# contra1568_X_Y.net
KiCad netlist of a schematic drawn in EAGLE
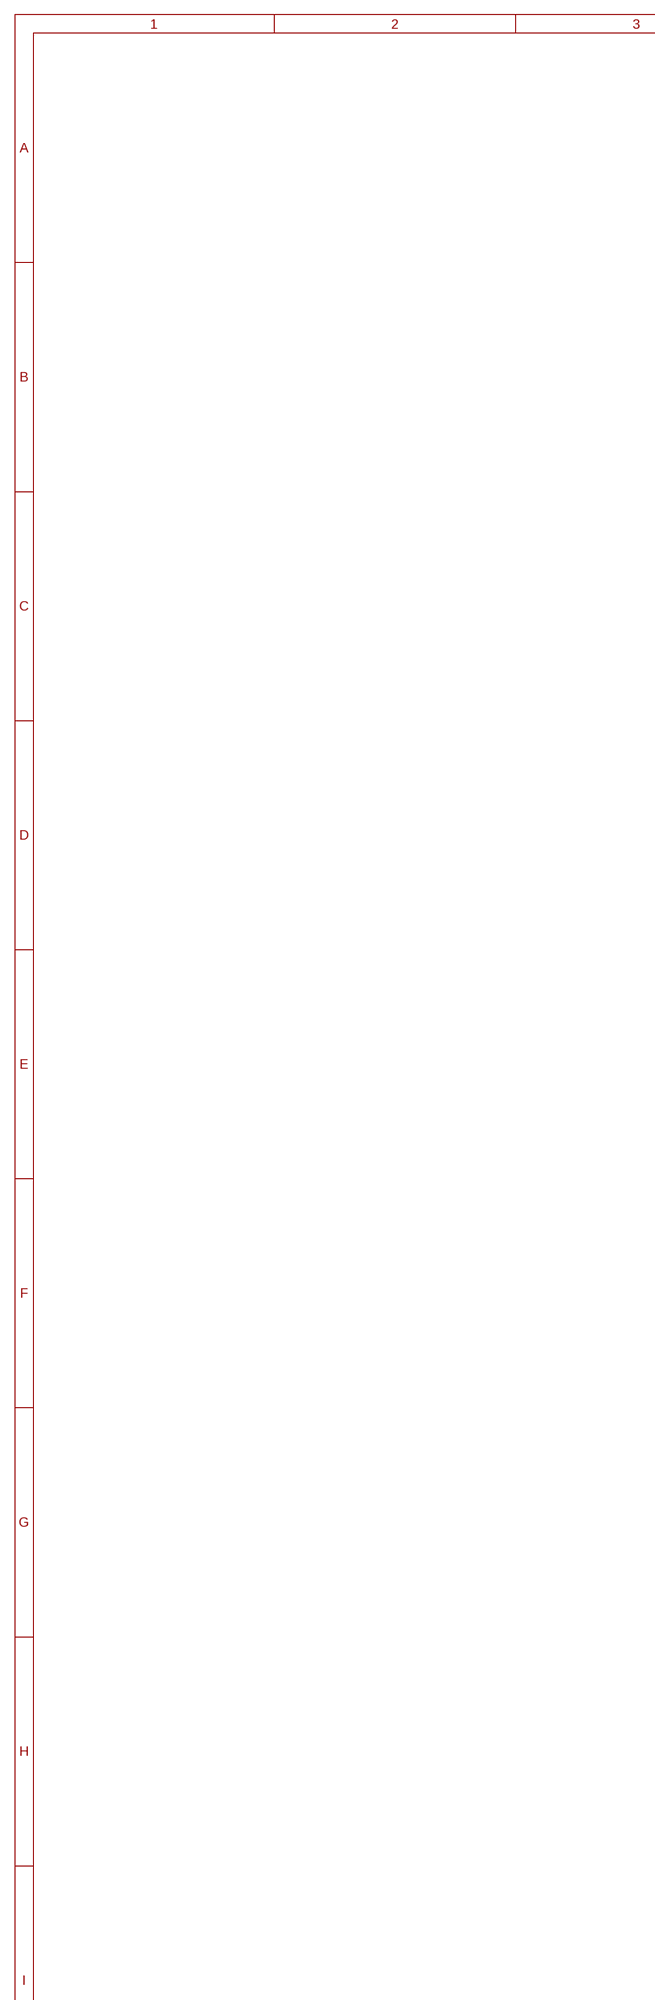
[diagram p0: schematic, sheet 1, part 1 of 2]
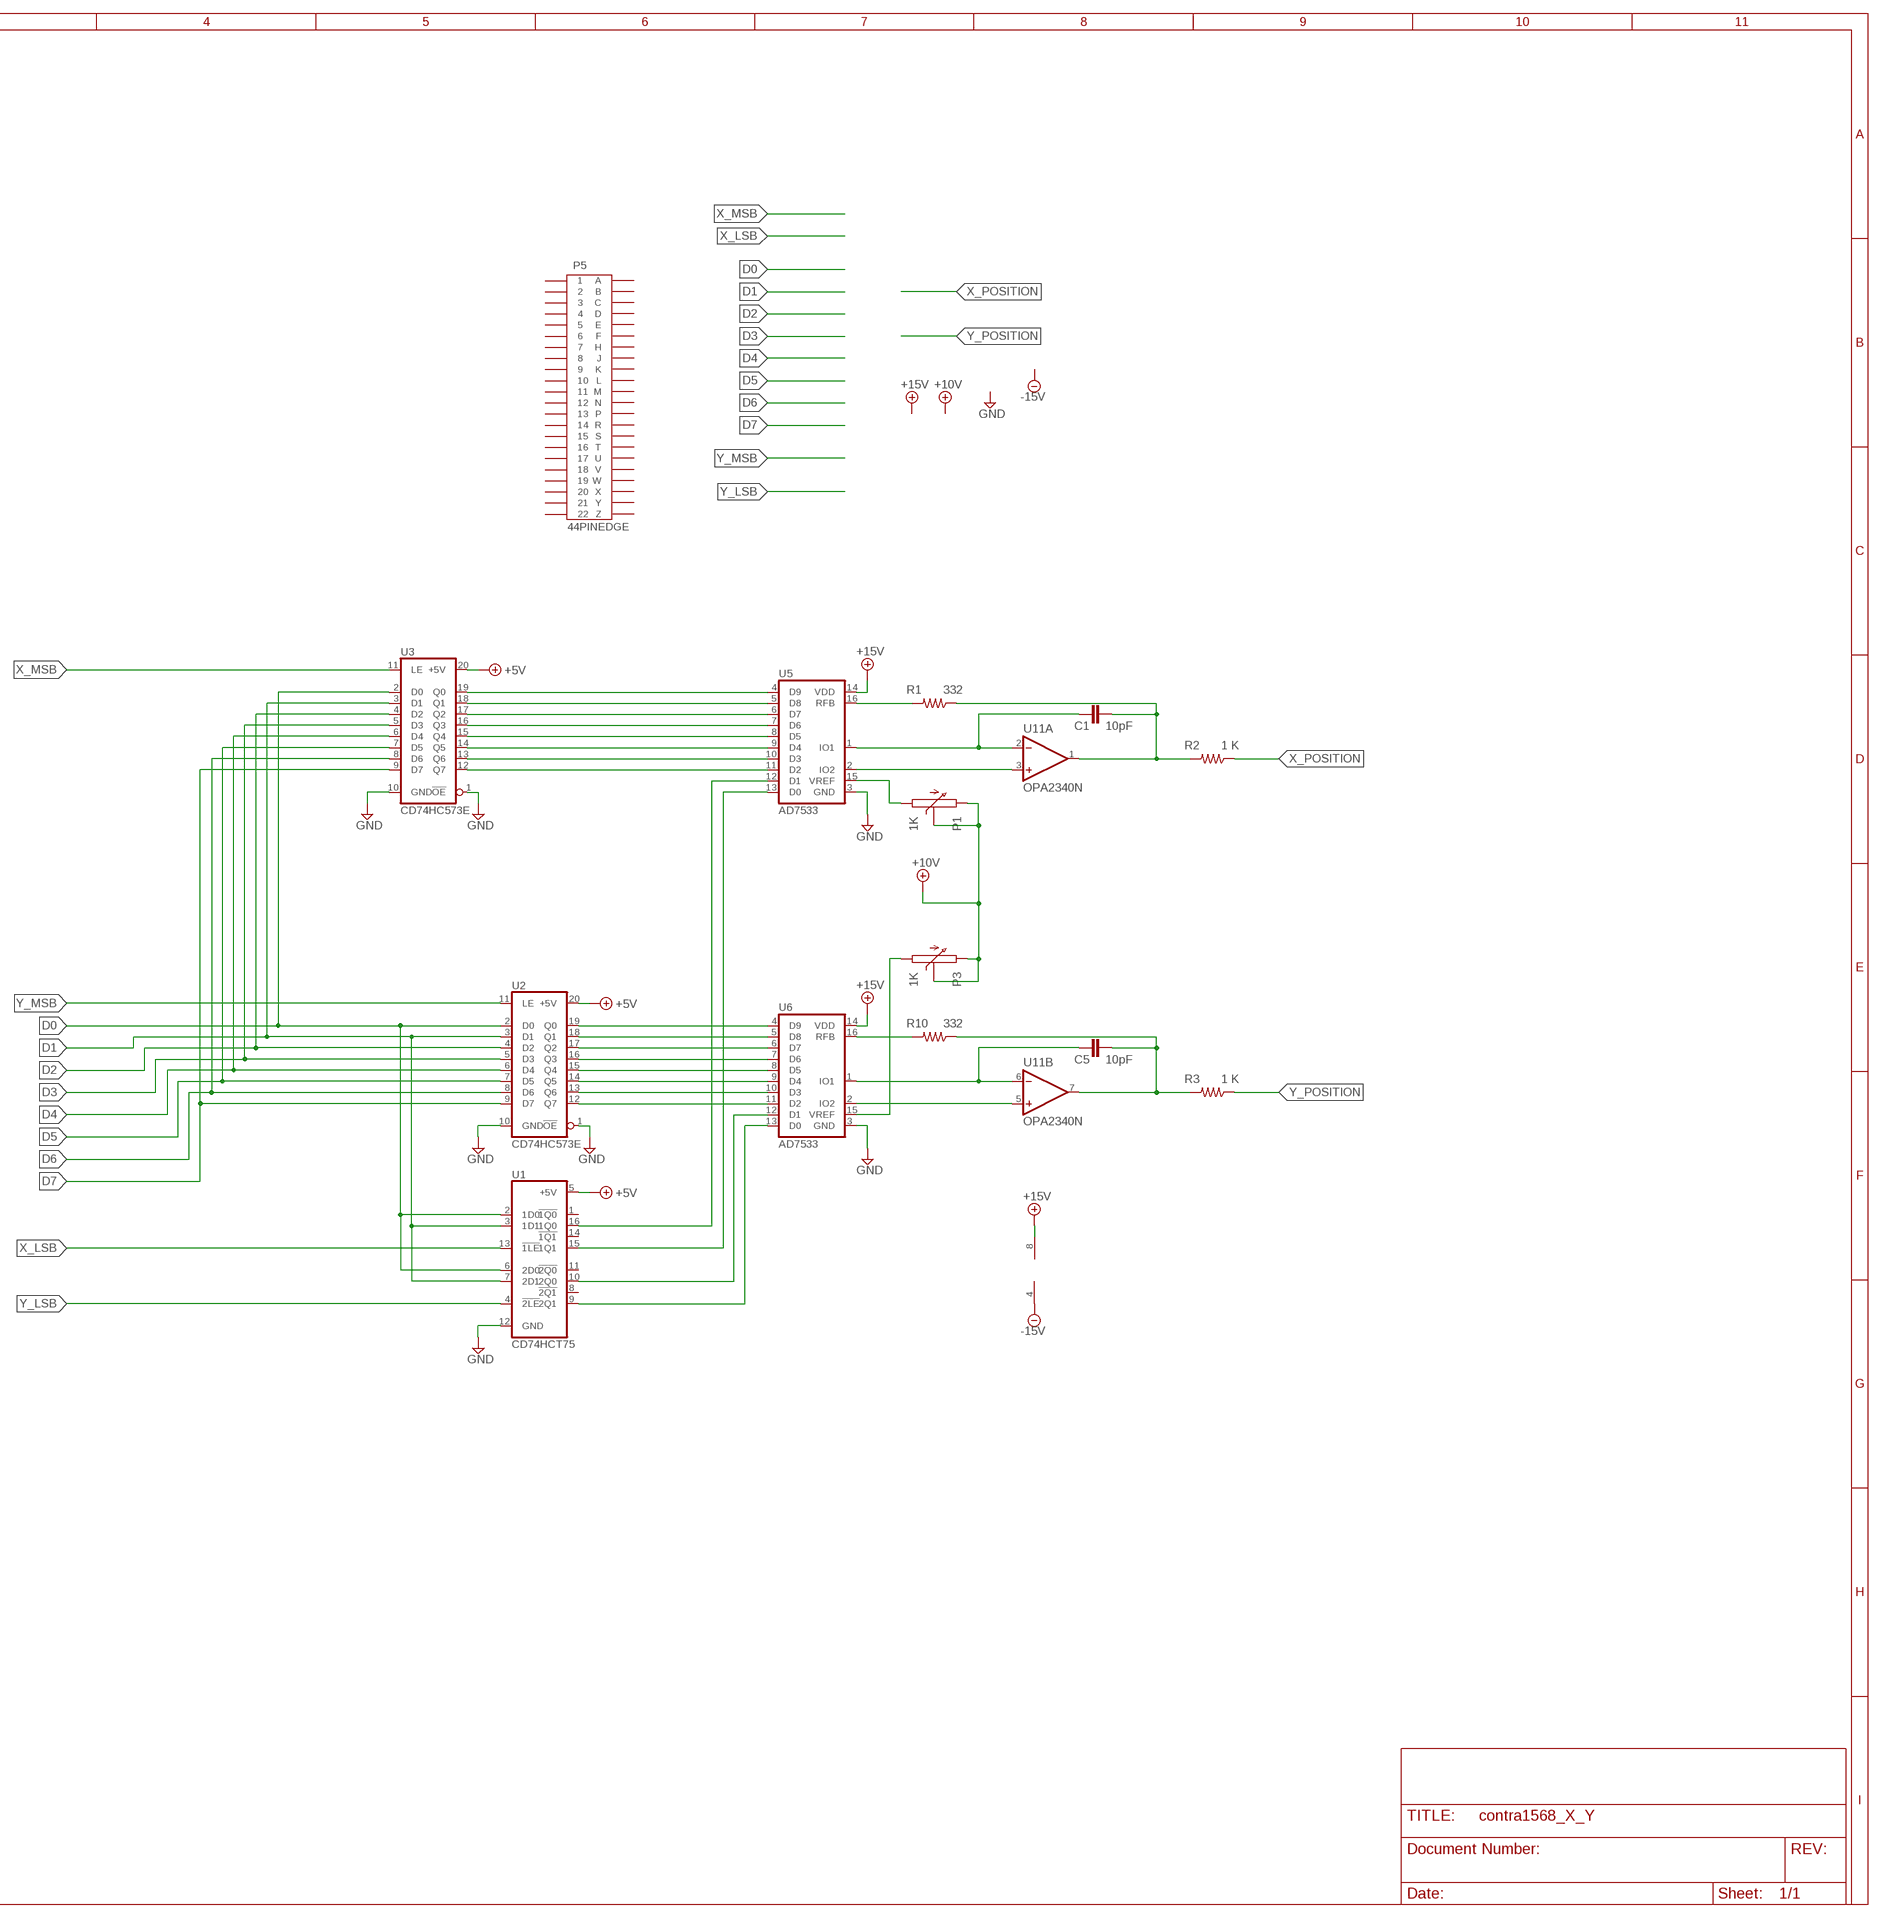
[diagram p1: schematic, sheet 1, part 2 of 2]

(export (version "E")
  (design (tool "Eeschema 10.0.6"))
  (components
    (comp (ref "C1")
      (value "10pF")
      (footprint "eagle-import:C2.5")
      (libsource (lib "eagle-import") (part "C-0.1"))
    )
    (comp (ref "C5")
      (value "10pF")
      (footprint "eagle-import:C2.5")
      (libsource (lib "eagle-import") (part "C-0.1"))
    )
    (comp (ref "P1")
      (value "1K")
      (footprint "eagle-import:3006P")
      (libsource (lib "eagle-import") (part "POT-3006P"))
    )
    (comp (ref "P3")
      (value "1K")
      (footprint "eagle-import:3006P")
      (libsource (lib "eagle-import") (part "POT-3006P"))
    )
    (comp (ref "P5")
      (value "44PINEDGE")
      (footprint "eagle-import:44PINEDGE")
      (libsource (lib "eagle-import") (part "44PINEDGE"))
    )
    (comp (ref "R1")
      (value "332")
      (footprint "eagle-import:0207_10")
      (libsource (lib "eagle-import") (part "R-1/4WATT"))
    )
    (comp (ref "R2")
      (value "1 K")
      (footprint "eagle-import:0207_10")
      (libsource (lib "eagle-import") (part "R-1/4WATT"))
    )
    (comp (ref "R3")
      (value "1 K")
      (footprint "eagle-import:0207_10")
      (libsource (lib "eagle-import") (part "R-1/4WATT"))
    )
    (comp (ref "R10")
      (value "332")
      (footprint "eagle-import:0207_10")
      (libsource (lib "eagle-import") (part "R-1/4WATT"))
    )
    (comp (ref "U1")
      (value "CD74HCT75")
      (footprint "eagle-import:DIP-16")
      (libsource (lib "eagle-import") (part "CD74HCT75"))
    )
    (comp (ref "U2")
      (value "CD74HC573E")
      (footprint "eagle-import:DIP-20")
      (libsource (lib "eagle-import") (part "CD74HC573E"))
    )
    (comp (ref "U3")
      (value "CD74HC573E")
      (footprint "eagle-import:DIP-20")
      (libsource (lib "eagle-import") (part "CD74HC573E"))
    )
    (comp (ref "U5")
      (value "AD7533")
      (footprint "eagle-import:DIP-16")
      (libsource (lib "eagle-import") (part "AD7533"))
    )
    (comp (ref "U6")
      (value "AD7533")
      (footprint "eagle-import:DIP-16")
      (libsource (lib "eagle-import") (part "AD7533"))
    )
    (comp (ref "U11")
      (value "OPA2340N")
      (footprint "eagle-import:DIP-08")
      (fields (field (name "PN") "OPA2340PA"))
      (libsource (lib "eagle-import") (part "OPA2340N"))
    )
  )
  (nets
    (net (code "1") (name "+5V") (class "Default")
      (node (ref "U1") (pin "5") (pinfunction "+5V_5") (pintype "power_in"))
      (node (ref "U2") (pin "20") (pinfunction "+5V_20") (pintype "power_in"))
      (node (ref "U3") (pin "20") (pinfunction "+5V_20") (pintype "power_in"))
    )
    (net (code "2") (name "+10V") (class "Default")
      (node (ref "P1") (pin "2") (pinfunction "S_2") (pintype "passive"))
      (node (ref "P1") (pin "3") (pinfunction "E_3") (pintype "passive"))
      (node (ref "P3") (pin "2") (pinfunction "S_2") (pintype "passive"))
      (node (ref "P3") (pin "3") (pinfunction "E_3") (pintype "passive"))
    )
    (net (code "3") (name "+15V") (class "Default")
      (node (ref "U11") (pin "8") (pinfunction "V+_8") (pintype "power_in"))
      (node (ref "U5") (pin "14") (pinfunction "VDD_14") (pintype "power_in"))
      (node (ref "U6") (pin "14") (pinfunction "VDD_14") (pintype "power_in"))
    )
    (net (code "4") (name "-15V") (class "Default")
      (node (ref "U11") (pin "4") (pinfunction "V-_4") (pintype "power_in"))
    )
    (net (code "5") (name "D0") (class "Default")
      (node (ref "U1") (pin "2") (pinfunction "1D0_2") (pintype "input"))
      (node (ref "U1") (pin "6") (pinfunction "2D0_6") (pintype "input"))
      (node (ref "U2") (pin "2") (pinfunction "D0_2") (pintype "input"))
      (node (ref "U3") (pin "2") (pinfunction "D0_2") (pintype "input"))
    )
    (net (code "6") (name "D1") (class "Default")
      (node (ref "U1") (pin "3") (pinfunction "1D1_3") (pintype "input"))
      (node (ref "U1") (pin "7") (pinfunction "2D1_7") (pintype "input"))
      (node (ref "U2") (pin "3") (pinfunction "D1_3") (pintype "input"))
      (node (ref "U3") (pin "3") (pinfunction "D1_3") (pintype "input"))
    )
    (net (code "7") (name "D2") (class "Default")
      (node (ref "U2") (pin "4") (pinfunction "D2_4") (pintype "input"))
      (node (ref "U3") (pin "4") (pinfunction "D2_4") (pintype "input"))
    )
    (net (code "8") (name "D3") (class "Default")
      (node (ref "U2") (pin "5") (pinfunction "D3_5") (pintype "input"))
      (node (ref "U3") (pin "5") (pinfunction "D3_5") (pintype "input"))
    )
    (net (code "9") (name "D4") (class "Default")
      (node (ref "U2") (pin "6") (pinfunction "D4_6") (pintype "input"))
      (node (ref "U3") (pin "6") (pinfunction "D4_6") (pintype "input"))
    )
    (net (code "10") (name "D5") (class "Default")
      (node (ref "U2") (pin "7") (pinfunction "D5_7") (pintype "input"))
      (node (ref "U3") (pin "7") (pinfunction "D5_7") (pintype "input"))
    )
    (net (code "11") (name "D6") (class "Default")
      (node (ref "U2") (pin "8") (pinfunction "D6_8") (pintype "input"))
      (node (ref "U3") (pin "8") (pinfunction "D6_8") (pintype "input"))
    )
    (net (code "12") (name "D7") (class "Default")
      (node (ref "U2") (pin "9") (pinfunction "D7_9") (pintype "input"))
      (node (ref "U3") (pin "9") (pinfunction "D7_9") (pintype "input"))
    )
    (net (code "13") (name "GND") (class "Default")
      (node (ref "U1") (pin "12") (pinfunction "GND_12") (pintype "power_in"))
      (node (ref "U2") (pin "1") (pinfunction "~{OE}_1") (pintype "input"))
      (node (ref "U2") (pin "10") (pinfunction "GND_10") (pintype "power_in"))
      (node (ref "U3") (pin "1") (pinfunction "~{OE}_1") (pintype "input"))
      (node (ref "U3") (pin "10") (pinfunction "GND_10") (pintype "power_in"))
      (node (ref "U5") (pin "3") (pinfunction "GND_3") (pintype "power_in"))
      (node (ref "U6") (pin "3") (pinfunction "GND_3") (pintype "power_in"))
    )
    (net (code "14") (name "Net-(P1-A)") (class "Default")
      (node (ref "P1") (pin "1") (pinfunction "A_1") (pintype "passive"))
      (node (ref "U5") (pin "15") (pinfunction "VREF_15") (pintype "power_in"))
    )
    (net (code "15") (name "Net-(P3-A)") (class "Default")
      (node (ref "P3") (pin "1") (pinfunction "A_1") (pintype "passive"))
      (node (ref "U6") (pin "15") (pinfunction "VREF_15") (pintype "power_in"))
    )
    (net (code "16") (name "Net-(R1-P$1)") (class "Default")
      (node (ref "C1") (pin "2") (pinfunction "2_2") (pintype "passive"))
      (node (ref "R1") (pin "1") (pinfunction "P$1_1") (pintype "passive"))
      (node (ref "R2") (pin "2") (pinfunction "P$2_2") (pintype "passive"))
      (node (ref "U11") (pin "1") (pinfunction "OUT_1") (pintype "output"))
    )
    (net (code "17") (name "Net-(R1-P$2)") (class "Default")
      (node (ref "R1") (pin "2") (pinfunction "P$2_2") (pintype "passive"))
      (node (ref "U5") (pin "16") (pinfunction "RFB_16") (pintype "input"))
    )
    (net (code "18") (name "Net-(R10-P$1)") (class "Default")
      (node (ref "C5") (pin "2") (pinfunction "2_2") (pintype "passive"))
      (node (ref "R10") (pin "1") (pinfunction "P$1_1") (pintype "passive"))
      (node (ref "R3") (pin "2") (pinfunction "P$2_2") (pintype "passive"))
      (node (ref "U11") (pin "7") (pinfunction "OUT_7") (pintype "output"))
    )
    (net (code "19") (name "Net-(R10-P$2)") (class "Default")
      (node (ref "R10") (pin "2") (pinfunction "P$2_2") (pintype "passive"))
      (node (ref "U6") (pin "16") (pinfunction "RFB_16") (pintype "input"))
    )
    (net (code "20") (name "Net-(U1-1Q0)") (class "Default")
      (node (ref "U1") (pin "16") (pinfunction "1Q0_16") (pintype "output"))
      (node (ref "U5") (pin "12") (pinfunction "D1_12") (pintype "input"))
    )
    (net (code "21") (name "Net-(U1-1Q1)") (class "Default")
      (node (ref "U1") (pin "15") (pinfunction "1Q1_15") (pintype "output"))
      (node (ref "U5") (pin "13") (pinfunction "D0_13") (pintype "input"))
    )
    (net (code "22") (name "Net-(U1-2Q0)") (class "Default")
      (node (ref "U1") (pin "10") (pinfunction "2Q0_10") (pintype "output"))
      (node (ref "U6") (pin "12") (pinfunction "D1_12") (pintype "input"))
    )
    (net (code "23") (name "Net-(U1-2Q1)") (class "Default")
      (node (ref "U1") (pin "9") (pinfunction "2Q1_9") (pintype "output"))
      (node (ref "U6") (pin "13") (pinfunction "D0_13") (pintype "input"))
    )
    (net (code "24") (name "Net-(U2-Q0)") (class "Default")
      (node (ref "U2") (pin "19") (pinfunction "Q0_19") (pintype "tri_state"))
      (node (ref "U6") (pin "4") (pinfunction "D9_4") (pintype "input"))
    )
    (net (code "25") (name "Net-(U2-Q1)") (class "Default")
      (node (ref "U2") (pin "18") (pinfunction "Q1_18") (pintype "tri_state"))
      (node (ref "U6") (pin "5") (pinfunction "D8_5") (pintype "input"))
    )
    (net (code "26") (name "Net-(U2-Q2)") (class "Default")
      (node (ref "U2") (pin "17") (pinfunction "Q2_17") (pintype "tri_state"))
      (node (ref "U6") (pin "6") (pinfunction "D7_6") (pintype "input"))
    )
    (net (code "27") (name "Net-(U2-Q3)") (class "Default")
      (node (ref "U2") (pin "16") (pinfunction "Q3_16") (pintype "tri_state"))
      (node (ref "U6") (pin "7") (pinfunction "D6_7") (pintype "input"))
    )
    (net (code "28") (name "Net-(U2-Q4)") (class "Default")
      (node (ref "U2") (pin "15") (pinfunction "Q4_15") (pintype "tri_state"))
      (node (ref "U6") (pin "8") (pinfunction "D5_8") (pintype "input"))
    )
    (net (code "29") (name "Net-(U2-Q5)") (class "Default")
      (node (ref "U2") (pin "14") (pinfunction "Q5_14") (pintype "tri_state"))
      (node (ref "U6") (pin "9") (pinfunction "D4_9") (pintype "input"))
    )
    (net (code "30") (name "Net-(U2-Q6)") (class "Default")
      (node (ref "U2") (pin "13") (pinfunction "Q6_13") (pintype "tri_state"))
      (node (ref "U6") (pin "10") (pinfunction "D3_10") (pintype "input"))
    )
    (net (code "31") (name "Net-(U2-Q7)") (class "Default")
      (node (ref "U2") (pin "12") (pinfunction "Q7_12") (pintype "tri_state"))
      (node (ref "U6") (pin "11") (pinfunction "D2_11") (pintype "input"))
    )
    (net (code "32") (name "Net-(U3-Q0)") (class "Default")
      (node (ref "U3") (pin "19") (pinfunction "Q0_19") (pintype "tri_state"))
      (node (ref "U5") (pin "4") (pinfunction "D9_4") (pintype "input"))
    )
    (net (code "33") (name "Net-(U3-Q1)") (class "Default")
      (node (ref "U3") (pin "18") (pinfunction "Q1_18") (pintype "tri_state"))
      (node (ref "U5") (pin "5") (pinfunction "D8_5") (pintype "input"))
    )
    (net (code "34") (name "Net-(U3-Q2)") (class "Default")
      (node (ref "U3") (pin "17") (pinfunction "Q2_17") (pintype "tri_state"))
      (node (ref "U5") (pin "6") (pinfunction "D7_6") (pintype "input"))
    )
    (net (code "35") (name "Net-(U3-Q3)") (class "Default")
      (node (ref "U3") (pin "16") (pinfunction "Q3_16") (pintype "tri_state"))
      (node (ref "U5") (pin "7") (pinfunction "D6_7") (pintype "input"))
    )
    (net (code "36") (name "Net-(U3-Q4)") (class "Default")
      (node (ref "U3") (pin "15") (pinfunction "Q4_15") (pintype "tri_state"))
      (node (ref "U5") (pin "8") (pinfunction "D5_8") (pintype "input"))
    )
    (net (code "37") (name "Net-(U3-Q5)") (class "Default")
      (node (ref "U3") (pin "14") (pinfunction "Q5_14") (pintype "tri_state"))
      (node (ref "U5") (pin "9") (pinfunction "D4_9") (pintype "input"))
    )
    (net (code "38") (name "Net-(U3-Q6)") (class "Default")
      (node (ref "U3") (pin "13") (pinfunction "Q6_13") (pintype "tri_state"))
      (node (ref "U5") (pin "10") (pinfunction "D3_10") (pintype "input"))
    )
    (net (code "39") (name "Net-(U3-Q7)") (class "Default")
      (node (ref "U3") (pin "12") (pinfunction "Q7_12") (pintype "tri_state"))
      (node (ref "U5") (pin "11") (pinfunction "D2_11") (pintype "input"))
    )
    (net (code "40") (name "Net-(U11A-+IN)") (class "Default")
      (node (ref "U11") (pin "3") (pinfunction "+IN_3") (pintype "input"))
      (node (ref "U5") (pin "2") (pinfunction "IO2_2") (pintype "output"))
    )
    (net (code "41") (name "Net-(U11A--IN)") (class "Default")
      (node (ref "C1") (pin "1") (pinfunction "1_1") (pintype "passive"))
      (node (ref "U11") (pin "2") (pinfunction "-IN_2") (pintype "input"))
      (node (ref "U5") (pin "1") (pinfunction "IO1_1") (pintype "output"))
    )
    (net (code "42") (name "Net-(U11B-+IN)") (class "Default")
      (node (ref "U11") (pin "5") (pinfunction "+IN_5") (pintype "input"))
      (node (ref "U6") (pin "2") (pinfunction "IO2_2") (pintype "output"))
    )
    (net (code "43") (name "Net-(U11B--IN)") (class "Default")
      (node (ref "C5") (pin "1") (pinfunction "1_1") (pintype "passive"))
      (node (ref "U11") (pin "6") (pinfunction "-IN_6") (pintype "input"))
      (node (ref "U6") (pin "1") (pinfunction "IO1_1") (pintype "output"))
    )
    (net (code "44") (name "X_LSB") (class "Default")
      (node (ref "U1") (pin "13") (pinfunction "~{1LE}_13") (pintype "input"))
    )
    (net (code "45") (name "X_MSB") (class "Default")
      (node (ref "U3") (pin "11") (pinfunction "LE_11") (pintype "input"))
    )
    (net (code "46") (name "X_POSITION") (class "Default")
      (node (ref "R2") (pin "1") (pinfunction "P$1_1") (pintype "passive"))
    )
    (net (code "47") (name "Y_LSB") (class "Default")
      (node (ref "U1") (pin "4") (pinfunction "~{2LE}_4") (pintype "input"))
    )
    (net (code "48") (name "Y_MSB") (class "Default")
      (node (ref "U2") (pin "11") (pinfunction "LE_11") (pintype "input"))
    )
    (net (code "49") (name "Y_POSITION") (class "Default")
      (node (ref "R3") (pin "1") (pinfunction "P$1_1") (pintype "passive"))
    )
    (net (code "50") (name "unconnected-(P5-Pad1)") (class "Default")
      (node (ref "P5") (pin "1") (pinfunction "1_1") (pintype "passive"))
    )
    (net (code "51") (name "unconnected-(P5-Pad2)") (class "Default")
      (node (ref "P5") (pin "2") (pinfunction "2_2") (pintype "passive"))
    )
    (net (code "52") (name "unconnected-(P5-Pad3)") (class "Default")
      (node (ref "P5") (pin "3") (pinfunction "3_3") (pintype "passive"))
    )
    (net (code "53") (name "unconnected-(P5-Pad4)") (class "Default")
      (node (ref "P5") (pin "4") (pinfunction "4_4") (pintype "passive"))
    )
    (net (code "54") (name "unconnected-(P5-Pad5)") (class "Default")
      (node (ref "P5") (pin "5") (pinfunction "5_5") (pintype "passive"))
    )
    (net (code "55") (name "unconnected-(P5-Pad6)") (class "Default")
      (node (ref "P5") (pin "6") (pinfunction "6_6") (pintype "passive"))
    )
    (net (code "56") (name "unconnected-(P5-Pad7)") (class "Default")
      (node (ref "P5") (pin "7") (pinfunction "7_7") (pintype "passive"))
    )
    (net (code "57") (name "unconnected-(P5-Pad8)") (class "Default")
      (node (ref "P5") (pin "8") (pinfunction "8_8") (pintype "passive"))
    )
    (net (code "58") (name "unconnected-(P5-Pad9)") (class "Default")
      (node (ref "P5") (pin "9") (pinfunction "9_9") (pintype "passive"))
    )
    (net (code "59") (name "unconnected-(P5-Pad10)") (class "Default")
      (node (ref "P5") (pin "10") (pinfunction "10_10") (pintype "passive"))
    )
    (net (code "60") (name "unconnected-(P5-Pad11)") (class "Default")
      (node (ref "P5") (pin "11") (pinfunction "11_11") (pintype "passive"))
    )
    (net (code "61") (name "unconnected-(P5-Pad12)") (class "Default")
      (node (ref "P5") (pin "12") (pinfunction "12_12") (pintype "passive"))
    )
    (net (code "62") (name "unconnected-(P5-Pad13)") (class "Default")
      (node (ref "P5") (pin "13") (pinfunction "13_13") (pintype "passive"))
    )
    (net (code "63") (name "unconnected-(P5-Pad14)") (class "Default")
      (node (ref "P5") (pin "14") (pinfunction "14_14") (pintype "passive"))
    )
    (net (code "64") (name "unconnected-(P5-Pad15)") (class "Default")
      (node (ref "P5") (pin "15") (pinfunction "15_15") (pintype "passive"))
    )
    (net (code "65") (name "unconnected-(P5-Pad16)") (class "Default")
      (node (ref "P5") (pin "16") (pinfunction "16_16") (pintype "passive"))
    )
    (net (code "66") (name "unconnected-(P5-Pad17)") (class "Default")
      (node (ref "P5") (pin "17") (pinfunction "17_17") (pintype "passive"))
    )
    (net (code "67") (name "unconnected-(P5-Pad18)") (class "Default")
      (node (ref "P5") (pin "18") (pinfunction "18_18") (pintype "passive"))
    )
    (net (code "68") (name "unconnected-(P5-Pad19)") (class "Default")
      (node (ref "P5") (pin "19") (pinfunction "19_19") (pintype "passive"))
    )
    (net (code "69") (name "unconnected-(P5-Pad20)") (class "Default")
      (node (ref "P5") (pin "20") (pinfunction "20_20") (pintype "passive"))
    )
    (net (code "70") (name "unconnected-(P5-Pad21)") (class "Default")
      (node (ref "P5") (pin "21") (pinfunction "21_21") (pintype "passive"))
    )
    (net (code "71") (name "unconnected-(P5-Pad22)") (class "Default")
      (node (ref "P5") (pin "22") (pinfunction "22_22") (pintype "passive"))
    )
    (net (code "72") (name "unconnected-(P5-PadA)") (class "Default")
      (node (ref "P5") (pin "A") (pinfunction "A_A") (pintype "passive"))
    )
    (net (code "73") (name "unconnected-(P5-PadB)") (class "Default")
      (node (ref "P5") (pin "B") (pinfunction "B_B") (pintype "passive"))
    )
    (net (code "74") (name "unconnected-(P5-PadC)") (class "Default")
      (node (ref "P5") (pin "C") (pinfunction "C_C") (pintype "passive"))
    )
    (net (code "75") (name "unconnected-(P5-PadD)") (class "Default")
      (node (ref "P5") (pin "D") (pinfunction "D_D") (pintype "passive"))
    )
    (net (code "76") (name "unconnected-(P5-PadE)") (class "Default")
      (node (ref "P5") (pin "E") (pinfunction "E_E") (pintype "passive"))
    )
    (net (code "77") (name "unconnected-(P5-PadF)") (class "Default")
      (node (ref "P5") (pin "F") (pinfunction "F_F") (pintype "passive"))
    )
    (net (code "78") (name "unconnected-(P5-PadH)") (class "Default")
      (node (ref "P5") (pin "H") (pinfunction "H_H") (pintype "passive"))
    )
    (net (code "79") (name "unconnected-(P5-PadJ)") (class "Default")
      (node (ref "P5") (pin "J") (pinfunction "J_J") (pintype "passive"))
    )
    (net (code "80") (name "unconnected-(P5-PadK)") (class "Default")
      (node (ref "P5") (pin "K") (pinfunction "K_K") (pintype "passive"))
    )
    (net (code "81") (name "unconnected-(P5-PadL)") (class "Default")
      (node (ref "P5") (pin "L") (pinfunction "L_L") (pintype "passive"))
    )
    (net (code "82") (name "unconnected-(P5-PadM)") (class "Default")
      (node (ref "P5") (pin "M") (pinfunction "M_M") (pintype "passive"))
    )
    (net (code "83") (name "unconnected-(P5-PadN)") (class "Default")
      (node (ref "P5") (pin "N") (pinfunction "N_N") (pintype "passive"))
    )
    (net (code "84") (name "unconnected-(P5-PadP)") (class "Default")
      (node (ref "P5") (pin "P") (pinfunction "P_P") (pintype "passive"))
    )
    (net (code "85") (name "unconnected-(P5-PadR)") (class "Default")
      (node (ref "P5") (pin "R") (pinfunction "R_R") (pintype "passive"))
    )
    (net (code "86") (name "unconnected-(P5-PadS)") (class "Default")
      (node (ref "P5") (pin "S") (pinfunction "S_S") (pintype "passive"))
    )
    (net (code "87") (name "unconnected-(P5-PadT)") (class "Default")
      (node (ref "P5") (pin "T") (pinfunction "T_T") (pintype "passive"))
    )
    (net (code "88") (name "unconnected-(P5-PadU)") (class "Default")
      (node (ref "P5") (pin "U") (pinfunction "U_U") (pintype "passive"))
    )
    (net (code "89") (name "unconnected-(P5-PadV)") (class "Default")
      (node (ref "P5") (pin "V") (pinfunction "V_V") (pintype "passive"))
    )
    (net (code "90") (name "unconnected-(P5-PadW)") (class "Default")
      (node (ref "P5") (pin "W") (pinfunction "W_W") (pintype "passive"))
    )
    (net (code "91") (name "unconnected-(P5-PadX)") (class "Default")
      (node (ref "P5") (pin "X") (pinfunction "X_X") (pintype "passive"))
    )
    (net (code "92") (name "unconnected-(P5-PadY)") (class "Default")
      (node (ref "P5") (pin "Y") (pinfunction "Y_Y") (pintype "passive"))
    )
    (net (code "93") (name "unconnected-(P5-PadZ)") (class "Default")
      (node (ref "P5") (pin "Z") (pinfunction "Z_Z") (pintype "passive"))
    )
    (net (code "94") (name "unconnected-(U1-~{1Q0}-Pad1)") (class "Default")
      (node (ref "U1") (pin "1") (pinfunction "~{1Q0}_1") (pintype "output"))
    )
    (net (code "95") (name "unconnected-(U1-~{1Q1}-Pad14)") (class "Default")
      (node (ref "U1") (pin "14") (pinfunction "~{1Q1}_14") (pintype "output"))
    )
    (net (code "96") (name "unconnected-(U1-~{2Q0}-Pad11)") (class "Default")
      (node (ref "U1") (pin "11") (pinfunction "~{2Q0}_11") (pintype "output"))
    )
    (net (code "97") (name "unconnected-(U1-~{2Q1}-Pad8)") (class "Default")
      (node (ref "U1") (pin "8") (pinfunction "~{2Q1}_8") (pintype "output"))
    )
  )
)
